# Task10_1PCB.net
KiCad netlist of a schematic drawn in EasyEDA
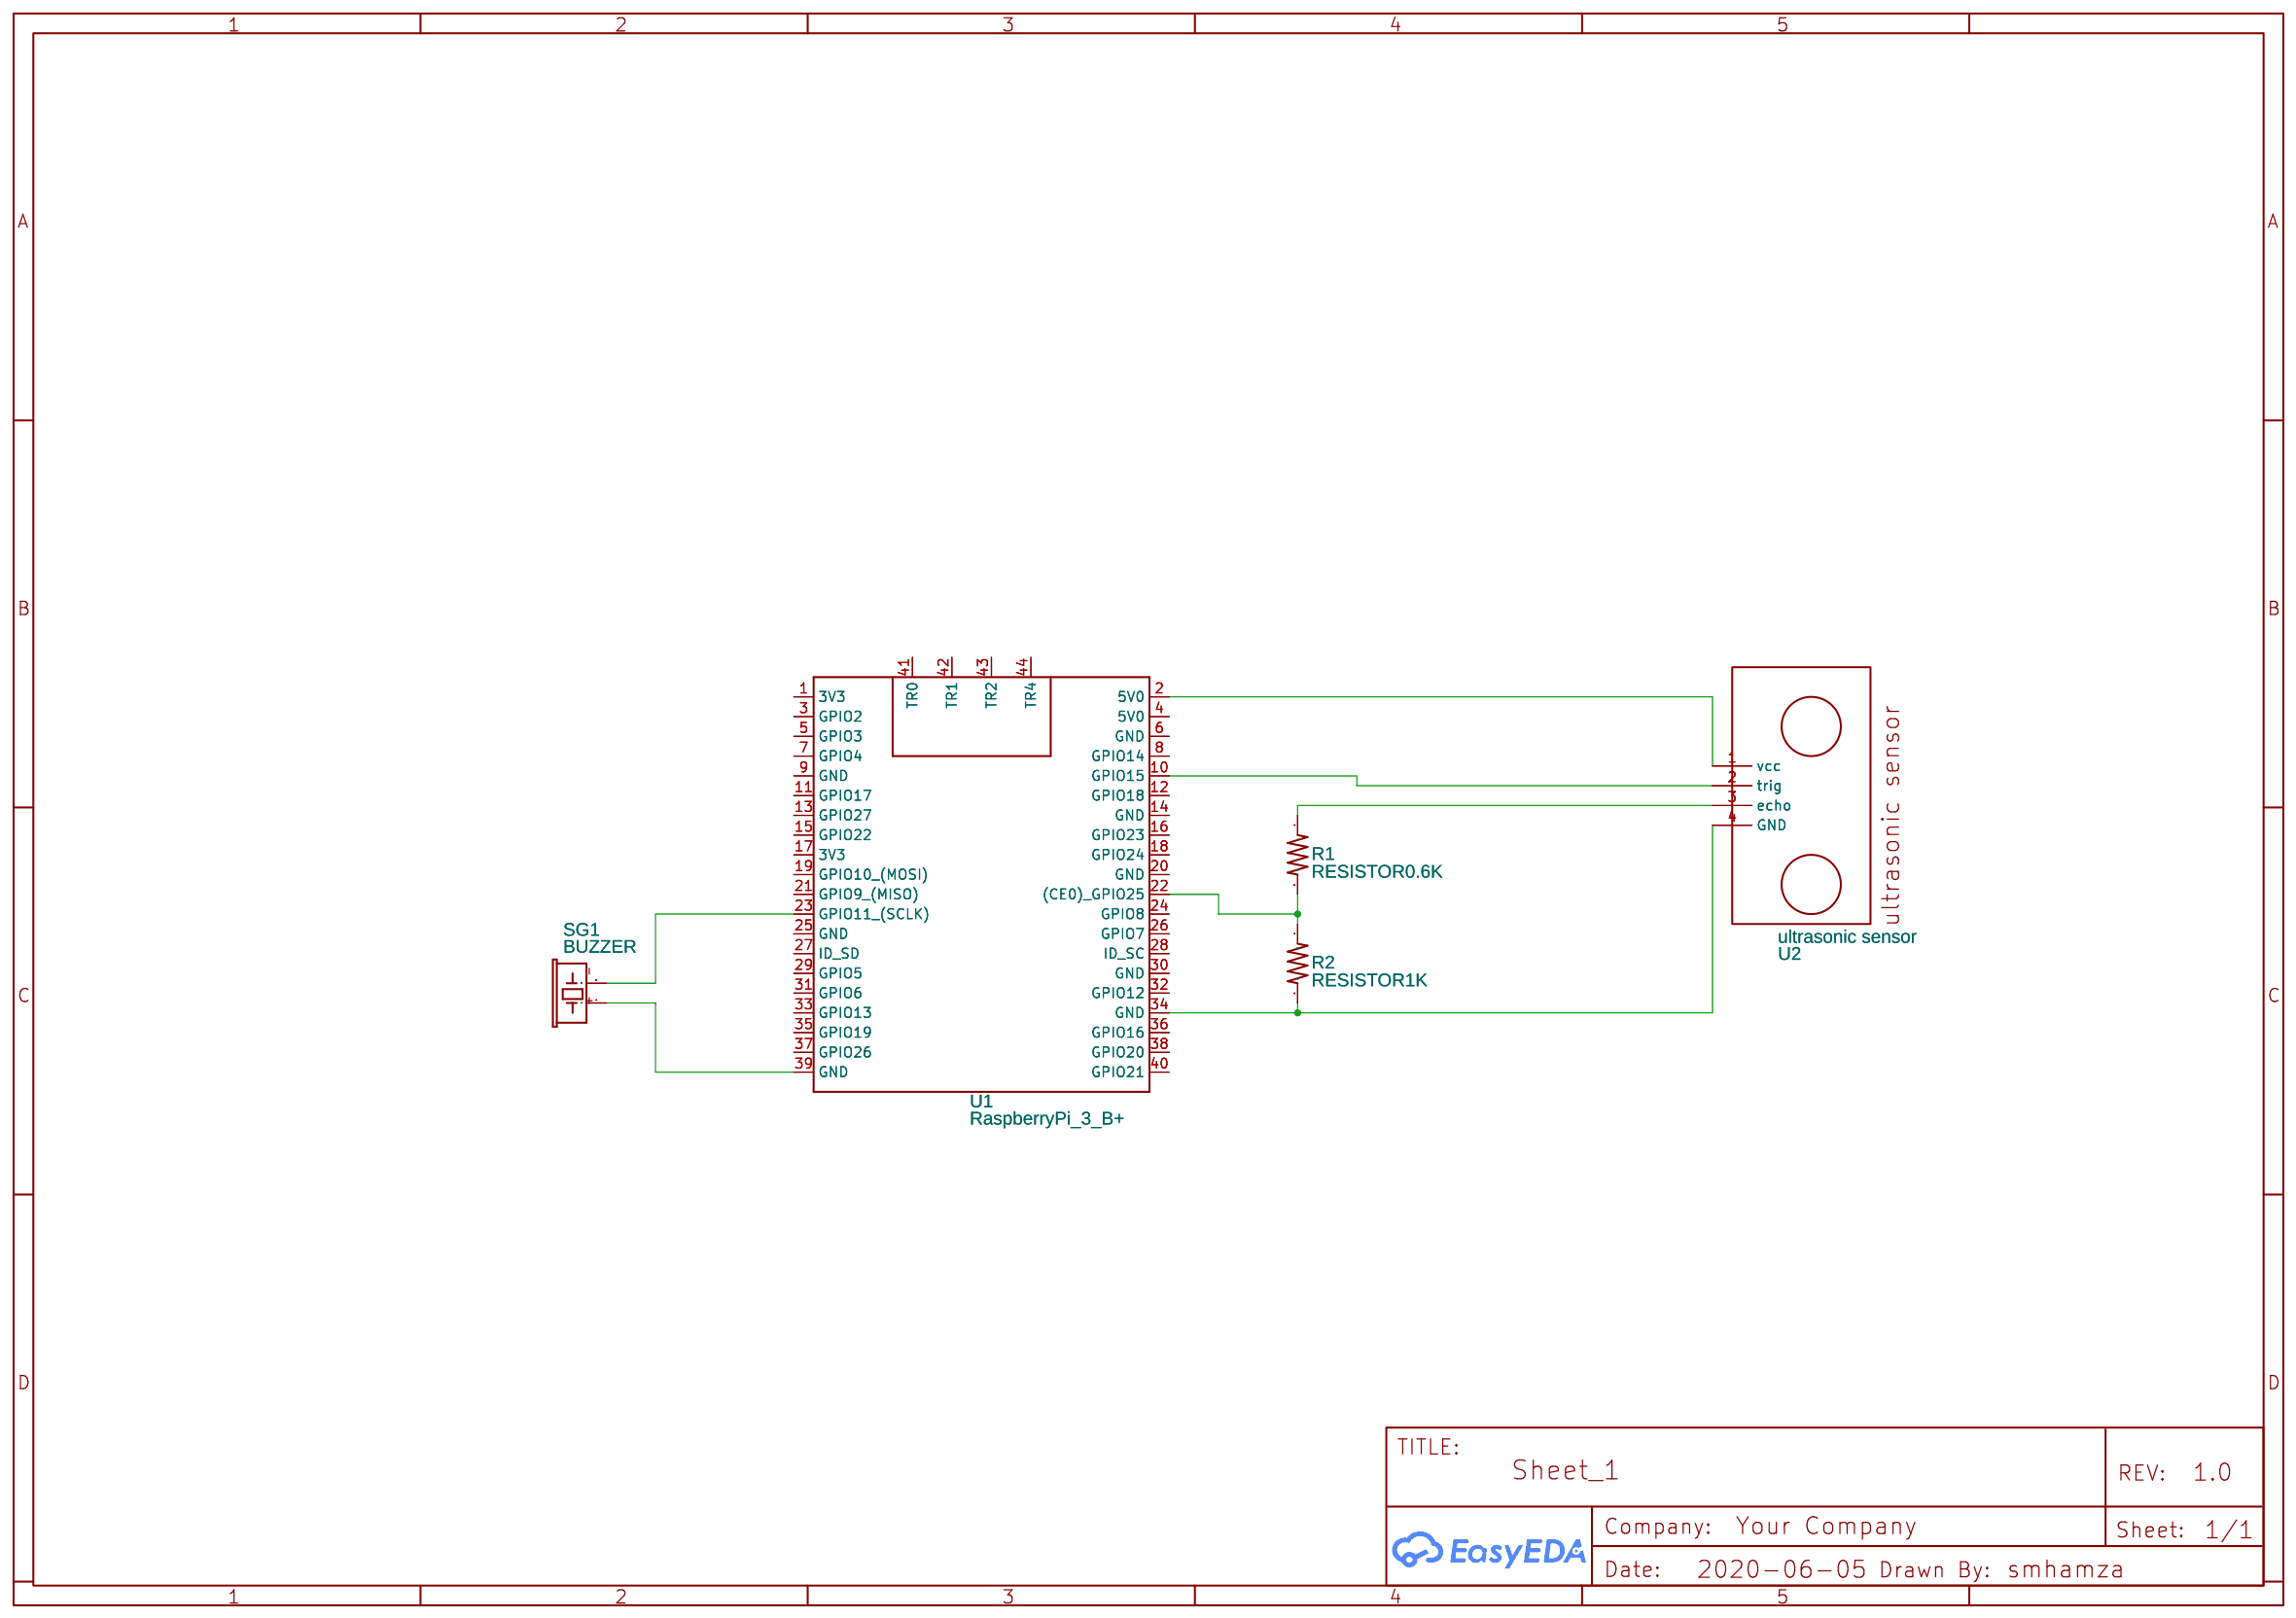
[diagram p0: schematic sheet]

(export (version "E")
  (design (tool "Eeschema 10.0.6"))
  (components
    (comp (ref "R1") (value "RESISTOR0.6K") (libsource (lib "") (part "RESISTOR1K")))
    (comp (ref "R2") (value "RESISTOR1K") (libsource (lib "") (part "RESISTOR1K")))
    (comp (ref "SG1") (value "BUZZER") (libsource (lib "") (part "BUZZER")))
    (comp (ref "U1")
      (value "RaspberryPi_3_B+")
      (fields (field (name "BOM_Manufacturer Part") "RaspberryPi 3"))
      (libsource (lib "") (part "RaspberryPi_3_B+"))
    )
    (comp (ref "U2") (value "ultrasonic sensor") (libsource (lib "") (part "ultrasonic sensor")))
  )
  (nets
    (net (code "1") (name "Net-(SG1-Pad1)") (class "Default")
      (node (ref "SG1") (pin "1") (pinfunction "1_1") (pintype "unspecified"))
      (node (ref "U1") (pin "39") (pinfunction "GND_39") (pintype "unspecified"))
    )
    (net (code "2") (name "Net-(U1-(CE0)_GPIO25)") (class "Default")
      (node (ref "R1") (pin "2") (pinfunction "2_2") (pintype "bidirectional"))
      (node (ref "R2") (pin "1") (pinfunction "1_1") (pintype "bidirectional"))
      (node (ref "U1") (pin "22") (pinfunction "(CE0)_GPIO25_22") (pintype "unspecified"))
    )
    (net (code "3") (name "Net-(U1-GPIO11_(SCLK))") (class "Default")
      (node (ref "SG1") (pin "2") (pinfunction "2_2") (pintype "unspecified"))
      (node (ref "U1") (pin "23") (pinfunction "GPIO11_(SCLK)_23") (pintype "unspecified"))
    )
    (net (code "4") (name "Net-(U1-GPIO15)") (class "Default")
      (node (ref "U1") (pin "10") (pinfunction "GPIO15_10") (pintype "unspecified"))
      (node (ref "U2") (pin "2") (pinfunction "trig_2") (pintype "unspecified"))
    )
    (net (code "5") (name "Net-(U2-GND)") (class "Default")
      (node (ref "R2") (pin "2") (pinfunction "2_2") (pintype "bidirectional"))
      (node (ref "U1") (pin "34") (pinfunction "GND_34") (pintype "unspecified"))
      (node (ref "U2") (pin "4") (pinfunction "GND_4") (pintype "unspecified"))
    )
    (net (code "6") (name "Net-(U2-echo)") (class "Default")
      (node (ref "R1") (pin "1") (pinfunction "1_1") (pintype "bidirectional"))
      (node (ref "U2") (pin "3") (pinfunction "echo_3") (pintype "unspecified"))
    )
    (net (code "7") (name "Net-(U2-vcc)") (class "Default")
      (node (ref "U1") (pin "2") (pinfunction "5V0_2") (pintype "unspecified"))
      (node (ref "U2") (pin "1") (pinfunction "vcc_1") (pintype "unspecified"))
    )
    (net (code "8") (name "unconnected-(U1-3V3-Pad1)") (class "Default")
      (node (ref "U1") (pin "1") (pinfunction "3V3_1") (pintype "unspecified"))
    )
    (net (code "9") (name "unconnected-(U1-3V3-Pad17)") (class "Default")
      (node (ref "U1") (pin "17") (pinfunction "3V3_17") (pintype "unspecified"))
    )
    (net (code "10") (name "unconnected-(U1-5V0-Pad4)") (class "Default")
      (node (ref "U1") (pin "4") (pinfunction "5V0_4") (pintype "unspecified"))
    )
    (net (code "11") (name "unconnected-(U1-GND-Pad6)") (class "Default")
      (node (ref "U1") (pin "6") (pinfunction "GND_6") (pintype "unspecified"))
    )
    (net (code "12") (name "unconnected-(U1-GND-Pad9)") (class "Default")
      (node (ref "U1") (pin "9") (pinfunction "GND_9") (pintype "unspecified"))
    )
    (net (code "13") (name "unconnected-(U1-GND-Pad14)") (class "Default")
      (node (ref "U1") (pin "14") (pinfunction "GND_14") (pintype "unspecified"))
    )
    (net (code "14") (name "unconnected-(U1-GND-Pad20)") (class "Default")
      (node (ref "U1") (pin "20") (pinfunction "GND_20") (pintype "unspecified"))
    )
    (net (code "15") (name "unconnected-(U1-GND-Pad25)") (class "Default")
      (node (ref "U1") (pin "25") (pinfunction "GND_25") (pintype "unspecified"))
    )
    (net (code "16") (name "unconnected-(U1-GND-Pad30)") (class "Default")
      (node (ref "U1") (pin "30") (pinfunction "GND_30") (pintype "unspecified"))
    )
    (net (code "17") (name "unconnected-(U1-GPIO2-Pad3)") (class "Default")
      (node (ref "U1") (pin "3") (pinfunction "GPIO2_3") (pintype "unspecified"))
    )
    (net (code "18") (name "unconnected-(U1-GPIO3-Pad5)") (class "Default")
      (node (ref "U1") (pin "5") (pinfunction "GPIO3_5") (pintype "unspecified"))
    )
    (net (code "19") (name "unconnected-(U1-GPIO4-Pad7)") (class "Default")
      (node (ref "U1") (pin "7") (pinfunction "GPIO4_7") (pintype "unspecified"))
    )
    (net (code "20") (name "unconnected-(U1-GPIO5-Pad29)") (class "Default")
      (node (ref "U1") (pin "29") (pinfunction "GPIO5_29") (pintype "unspecified"))
    )
    (net (code "21") (name "unconnected-(U1-GPIO6-Pad31)") (class "Default")
      (node (ref "U1") (pin "31") (pinfunction "GPIO6_31") (pintype "unspecified"))
    )
    (net (code "22") (name "unconnected-(U1-GPIO7-Pad26)") (class "Default")
      (node (ref "U1") (pin "26") (pinfunction "GPIO7_26") (pintype "unspecified"))
    )
    (net (code "23") (name "unconnected-(U1-GPIO8-Pad24)") (class "Default")
      (node (ref "U1") (pin "24") (pinfunction "GPIO8_24") (pintype "unspecified"))
    )
    (net (code "24") (name "unconnected-(U1-GPIO9_(MISO)-Pad21)") (class "Default")
      (node (ref "U1") (pin "21") (pinfunction "GPIO9_(MISO)_21") (pintype "unspecified"))
    )
    (net (code "25") (name "unconnected-(U1-GPIO10_(MOSI)-Pad19)") (class "Default")
      (node (ref "U1") (pin "19") (pinfunction "GPIO10_(MOSI)_19") (pintype "unspecified"))
    )
    (net (code "26") (name "unconnected-(U1-GPIO12-Pad32)") (class "Default")
      (node (ref "U1") (pin "32") (pinfunction "GPIO12_32") (pintype "unspecified"))
    )
    (net (code "27") (name "unconnected-(U1-GPIO13-Pad33)") (class "Default")
      (node (ref "U1") (pin "33") (pinfunction "GPIO13_33") (pintype "unspecified"))
    )
    (net (code "28") (name "unconnected-(U1-GPIO14-Pad8)") (class "Default")
      (node (ref "U1") (pin "8") (pinfunction "GPIO14_8") (pintype "unspecified"))
    )
    (net (code "29") (name "unconnected-(U1-GPIO16-Pad36)") (class "Default")
      (node (ref "U1") (pin "36") (pinfunction "GPIO16_36") (pintype "unspecified"))
    )
    (net (code "30") (name "unconnected-(U1-GPIO17-Pad11)") (class "Default")
      (node (ref "U1") (pin "11") (pinfunction "GPIO17_11") (pintype "unspecified"))
    )
    (net (code "31") (name "unconnected-(U1-GPIO18-Pad12)") (class "Default")
      (node (ref "U1") (pin "12") (pinfunction "GPIO18_12") (pintype "unspecified"))
    )
    (net (code "32") (name "unconnected-(U1-GPIO19-Pad35)") (class "Default")
      (node (ref "U1") (pin "35") (pinfunction "GPIO19_35") (pintype "unspecified"))
    )
    (net (code "33") (name "unconnected-(U1-GPIO20-Pad38)") (class "Default")
      (node (ref "U1") (pin "38") (pinfunction "GPIO20_38") (pintype "unspecified"))
    )
    (net (code "34") (name "unconnected-(U1-GPIO21-Pad40)") (class "Default")
      (node (ref "U1") (pin "40") (pinfunction "GPIO21_40") (pintype "unspecified"))
    )
    (net (code "35") (name "unconnected-(U1-GPIO22-Pad15)") (class "Default")
      (node (ref "U1") (pin "15") (pinfunction "GPIO22_15") (pintype "unspecified"))
    )
    (net (code "36") (name "unconnected-(U1-GPIO23-Pad16)") (class "Default")
      (node (ref "U1") (pin "16") (pinfunction "GPIO23_16") (pintype "unspecified"))
    )
    (net (code "37") (name "unconnected-(U1-GPIO24-Pad18)") (class "Default")
      (node (ref "U1") (pin "18") (pinfunction "GPIO24_18") (pintype "unspecified"))
    )
    (net (code "38") (name "unconnected-(U1-GPIO26-Pad37)") (class "Default")
      (node (ref "U1") (pin "37") (pinfunction "GPIO26_37") (pintype "unspecified"))
    )
    (net (code "39") (name "unconnected-(U1-GPIO27-Pad13)") (class "Default")
      (node (ref "U1") (pin "13") (pinfunction "GPIO27_13") (pintype "unspecified"))
    )
    (net (code "40") (name "unconnected-(U1-ID_SC-Pad28)") (class "Default")
      (node (ref "U1") (pin "28") (pinfunction "ID_SC_28") (pintype "unspecified"))
    )
    (net (code "41") (name "unconnected-(U1-ID_SD-Pad27)") (class "Default")
      (node (ref "U1") (pin "27") (pinfunction "ID_SD_27") (pintype "unspecified"))
    )
    (net (code "42") (name "unconnected-(U1-TR0-Pad41)") (class "Default")
      (node (ref "U1") (pin "41") (pinfunction "TR0_41") (pintype "unspecified"))
    )
    (net (code "43") (name "unconnected-(U1-TR1-Pad42)") (class "Default")
      (node (ref "U1") (pin "42") (pinfunction "TR1_42") (pintype "unspecified"))
    )
    (net (code "44") (name "unconnected-(U1-TR2-Pad43)") (class "Default")
      (node (ref "U1") (pin "43") (pinfunction "TR2_43") (pintype "unspecified"))
    )
    (net (code "45") (name "unconnected-(U1-TR4-Pad44)") (class "Default")
      (node (ref "U1") (pin "44") (pinfunction "TR4_44") (pintype "unspecified"))
    )
  )
)
